# AD8302.net
KiCad netlist of a schematic drawn in Altium Designer
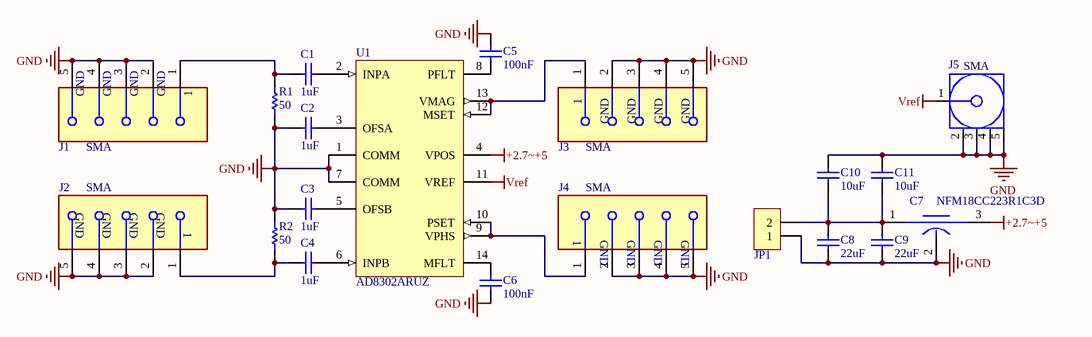
[diagram p0: AD8302.SchDoc]

(export (version "E")
  (design (tool "Eeschema 10.0.6"))
  (components
    (comp (ref "C1")
      (value "1uF")
      (footprint "0603_C")
      (description "Capacitor")
      (fields (field (name "PUBLISHER") "Altium Limited"))
      (libsource (lib "My Footprint") (part "CAP"))
    )
    (comp (ref "C2")
      (value "1uF")
      (footprint "0603_C")
      (description "Capacitor")
      (fields (field (name "PUBLISHER") "Altium Limited"))
      (libsource (lib "My Footprint") (part "CAP"))
    )
    (comp (ref "C3")
      (value "1uF")
      (footprint "0603_C")
      (description "Capacitor")
      (fields (field (name "PUBLISHER") "Altium Limited"))
      (libsource (lib "My Footprint") (part "CAP"))
    )
    (comp (ref "C4")
      (value "1uF")
      (footprint "0603_C")
      (description "Capacitor")
      (fields (field (name "PUBLISHER") "Altium Limited"))
      (libsource (lib "My Footprint") (part "CAP"))
    )
    (comp (ref "C5")
      (value "100nF")
      (footprint "0603_C")
      (description "Capacitor")
      (fields (field (name "PUBLISHER") "Altium Limited"))
      (libsource (lib "My Footprint") (part "CAP"))
    )
    (comp (ref "C6")
      (value "100nF")
      (footprint "0603_C")
      (description "Capacitor")
      (fields (field (name "PUBLISHER") "Altium Limited"))
      (libsource (lib "My Footprint") (part "CAP"))
    )
    (comp (ref "C7")
      (value "NFM18CC223R1C3D")
      (footprint "FP-NFM18-0_1-e0_15_0_35-MFG")
      (fields (field (name "TOLERANCE") "20%") (field (name "VOLTAGE") "16V"))
      (libsource (lib "NFM18CC223R1C3") (part "CMP-06053-000245-1"))
    )
    (comp (ref "C8")
      (value "22uF")
      (footprint "0805_C")
      (description "Capacitor")
      (fields (field (name "PUBLISHER") "Altium Limited"))
      (libsource (lib "My Footprint") (part "CAP"))
    )
    (comp (ref "C9")
      (value "22uF")
      (footprint "0805_C")
      (description "Capacitor")
      (fields (field (name "PUBLISHER") "Altium Limited"))
      (libsource (lib "My Footprint") (part "CAP"))
    )
    (comp (ref "C10")
      (value "10uF")
      (footprint "0603_C")
      (description "Capacitor")
      (fields (field (name "PUBLISHER") "Altium Limited"))
      (libsource (lib "My Footprint") (part "CAP"))
    )
    (comp (ref "C11")
      (value "10uF")
      (footprint "0603_C")
      (description "Capacitor")
      (fields (field (name "PUBLISHER") "Altium Limited"))
      (libsource (lib "My Footprint") (part "CAP"))
    )
    (comp (ref "J1")
      (value "SMA")
      (footprint "FP-SMA-J-P-H-ST-EM1-MFG")
      (description "CONN SMA JACK STR 50OHM EDGE MNT")
      (libsource (lib "SMA_Side") (part "CMP-02754-000006-1"))
    )
    (comp (ref "J2")
      (value "SMA")
      (footprint "FP-SMA-J-P-H-ST-EM1-MFG")
      (description "CONN SMA JACK STR 50OHM EDGE MNT")
      (libsource (lib "") (part "CMP-02754-000006-1_2"))
    )
    (comp (ref "J3")
      (value "SMA")
      (footprint "FP-SMA-J-P-H-ST-EM1-MFG")
      (description "CONN SMA JACK STR 50OHM EDGE MNT")
      (libsource (lib "") (part "CMP-02754-000006-1_3"))
    )
    (comp (ref "J4")
      (value "SMA")
      (footprint "FP-SMA-J-P-H-ST-EM1-MFG")
      (description "CONN SMA JACK STR 50OHM EDGE MNT")
      (libsource (lib "") (part "CMP-02754-000006-1_1"))
    )
    (comp (ref "J5")
      (value "SMA")
      (footprint "TECO-5-1814832-1_V")
      (fields (field (name "MANUFACTURER") "TE Connectivity"))
      (libsource (lib "SMA_Straight") (part "CMP-2000-05415-1"))
    )
    (comp (ref "JP1")
      (value "HDR-1X2")
      (footprint "KF2510-LI-2P")
      (description "2P接插件")
      (libsource (lib "2510_2P") (part "Header 2"))
    )
    (comp (ref "R1")
      (value "50")
      (footprint "RES_MMA0204_3P6X1P4_VIS-L")
      (description "Resistor")
      (fields (field (name "PUBLISHER") "Altium Limited"))
      (libsource (lib "My Footprint") (part "RES"))
    )
    (comp (ref "R2")
      (value "50")
      (footprint "RES_MMA0204_3P6X1P4_VIS-L")
      (description "Resistor")
      (fields (field (name "PUBLISHER") "Altium Limited"))
      (libsource (lib "My Footprint") (part "RES"))
    )
    (comp (ref "U1")
      (value "AD8302ARUZ")
      (footprint "ADI-RU-14_L")
      (description "LF-2.7 GHz RF/IF Gain and Phase Detector, 60ns Response Time, RU-14, Pb-Free, 96 Tube")
      (libsource (lib "AD8302") (part "CMP-0284-00076-1"))
    )
  )
  (nets
    (net (code "1") (name "+2.7~+5") (class "Default")
      (node (ref "C7") (pin "3") (pinfunction "Output_3") (pintype "passive"))
      (node (ref "U1") (pin "4") (pinfunction "VPOS_4") (pintype "power_in"))
    )
    (net (code "2") (name "GND") (class "Default")
      (node (ref "C10") (pin "1") (pinfunction "1_1") (pintype "passive"))
      (node (ref "C11") (pin "1") (pinfunction "1_1") (pintype "passive"))
      (node (ref "C2") (pin "1") (pinfunction "1_1") (pintype "passive"))
      (node (ref "C3") (pin "1") (pinfunction "1_1") (pintype "passive"))
      (node (ref "C5") (pin "1") (pinfunction "1_1") (pintype "passive"))
      (node (ref "C6") (pin "2") (pinfunction "2_2") (pintype "passive"))
      (node (ref "C7") (pin "2") (pinfunction "GND_2") (pintype "passive"))
      (node (ref "C8") (pin "2") (pinfunction "2_2") (pintype "passive"))
      (node (ref "C9") (pin "2") (pinfunction "2_2") (pintype "passive"))
      (node (ref "J1") (pin "2") (pinfunction "MNT_1_2") (pintype "passive"))
      (node (ref "J1") (pin "3") (pinfunction "MNT_2_3") (pintype "passive"))
      (node (ref "J1") (pin "4") (pinfunction "MNT_3_4") (pintype "passive"))
      (node (ref "J1") (pin "5") (pinfunction "MNT_4_5") (pintype "passive"))
      (node (ref "J2") (pin "2") (pinfunction "MNT_1_2") (pintype "passive"))
      (node (ref "J2") (pin "3") (pinfunction "MNT_2_3") (pintype "passive"))
      (node (ref "J2") (pin "4") (pinfunction "MNT_3_4") (pintype "passive"))
      (node (ref "J2") (pin "5") (pinfunction "MNT_4_5") (pintype "passive"))
      (node (ref "J3") (pin "2") (pinfunction "MNT_1_2") (pintype "passive"))
      (node (ref "J3") (pin "3") (pinfunction "MNT_2_3") (pintype "passive"))
      (node (ref "J3") (pin "4") (pinfunction "MNT_3_4") (pintype "passive"))
      (node (ref "J3") (pin "5") (pinfunction "MNT_4_5") (pintype "passive"))
      (node (ref "J4") (pin "2") (pinfunction "MNT_1_2") (pintype "passive"))
      (node (ref "J4") (pin "3") (pinfunction "MNT_2_3") (pintype "passive"))
      (node (ref "J4") (pin "4") (pinfunction "MNT_3_4") (pintype "passive"))
      (node (ref "J4") (pin "5") (pinfunction "MNT_4_5") (pintype "passive"))
      (node (ref "J5") (pin "2") (pinfunction "2_2") (pintype "passive"))
      (node (ref "J5") (pin "3") (pinfunction "3_3") (pintype "passive"))
      (node (ref "J5") (pin "4") (pinfunction "4_4") (pintype "passive"))
      (node (ref "J5") (pin "5") (pinfunction "5_5") (pintype "passive"))
      (node (ref "JP1") (pin "1") (pinfunction "1_1") (pintype "passive"))
      (node (ref "R1") (pin "2") (pinfunction "2_2") (pintype "passive"))
      (node (ref "R2") (pin "1") (pinfunction "1_1") (pintype "passive"))
      (node (ref "U1") (pin "1") (pinfunction "COMM_1") (pintype "power_in"))
      (node (ref "U1") (pin "7") (pinfunction "COMM_7") (pintype "power_in"))
    )
    (net (code "3") (name "Net-(C1-Pad1)") (class "Default")
      (node (ref "C1") (pin "1") (pinfunction "1_1") (pintype "passive"))
      (node (ref "J1") (pin "1") (pinfunction "1_1") (pintype "passive"))
      (node (ref "R1") (pin "1") (pinfunction "1_1") (pintype "passive"))
    )
    (net (code "4") (name "Net-(C4-Pad1)") (class "Default")
      (node (ref "C4") (pin "1") (pinfunction "1_1") (pintype "passive"))
      (node (ref "J2") (pin "1") (pinfunction "1_1") (pintype "passive"))
      (node (ref "R2") (pin "2") (pinfunction "2_2") (pintype "passive"))
    )
    (net (code "5") (name "Net-(C7-Input)") (class "Default")
      (node (ref "C10") (pin "2") (pinfunction "2_2") (pintype "passive"))
      (node (ref "C11") (pin "2") (pinfunction "2_2") (pintype "passive"))
      (node (ref "C7") (pin "1") (pinfunction "Input_1") (pintype "passive"))
      (node (ref "C8") (pin "1") (pinfunction "1_1") (pintype "passive"))
      (node (ref "C9") (pin "1") (pinfunction "1_1") (pintype "passive"))
      (node (ref "JP1") (pin "2") (pinfunction "2_2") (pintype "passive"))
    )
    (net (code "6") (name "Net-(U1-INPA)") (class "Default")
      (node (ref "C1") (pin "2") (pinfunction "2_2") (pintype "passive"))
      (node (ref "U1") (pin "2") (pinfunction "INPA_2") (pintype "input"))
    )
    (net (code "7") (name "Net-(U1-INPB)") (class "Default")
      (node (ref "C4") (pin "2") (pinfunction "2_2") (pintype "passive"))
      (node (ref "U1") (pin "6") (pinfunction "INPB_6") (pintype "input"))
    )
    (net (code "8") (name "Net-(U1-MFLT)") (class "Default")
      (node (ref "C6") (pin "1") (pinfunction "1_1") (pintype "passive"))
      (node (ref "U1") (pin "14") (pinfunction "MFLT_14") (pintype "passive"))
    )
    (net (code "9") (name "Net-(U1-MSET)") (class "Default")
      (node (ref "J3") (pin "1") (pinfunction "1_1") (pintype "passive"))
      (node (ref "U1") (pin "12") (pinfunction "MSET_12") (pintype "input"))
      (node (ref "U1") (pin "13") (pinfunction "VMAG_13") (pintype "output"))
    )
    (net (code "10") (name "Net-(U1-OFSA)") (class "Default")
      (node (ref "C2") (pin "2") (pinfunction "2_2") (pintype "passive"))
      (node (ref "U1") (pin "3") (pinfunction "OFSA_3") (pintype "passive"))
    )
    (net (code "11") (name "Net-(U1-OFSB)") (class "Default")
      (node (ref "C3") (pin "2") (pinfunction "2_2") (pintype "passive"))
      (node (ref "U1") (pin "5") (pinfunction "OFSB_5") (pintype "passive"))
    )
    (net (code "12") (name "Net-(U1-PFLT)") (class "Default")
      (node (ref "C5") (pin "2") (pinfunction "2_2") (pintype "passive"))
      (node (ref "U1") (pin "8") (pinfunction "PFLT_8") (pintype "passive"))
    )
    (net (code "13") (name "Net-(U1-PSET)") (class "Default")
      (node (ref "J4") (pin "1") (pinfunction "1_1") (pintype "passive"))
      (node (ref "U1") (pin "10") (pinfunction "PSET_10") (pintype "input"))
      (node (ref "U1") (pin "9") (pinfunction "VPHS_9") (pintype "output"))
    )
    (net (code "14") (name "Vref") (class "Default")
      (node (ref "J5") (pin "1") (pinfunction "1_1") (pintype "passive"))
      (node (ref "U1") (pin "11") (pinfunction "VREF_11") (pintype "power_in"))
    )
  )
)
